# OSO-SWAT-A1-00.net
KiCad netlist of a schematic drawn in EAGLE
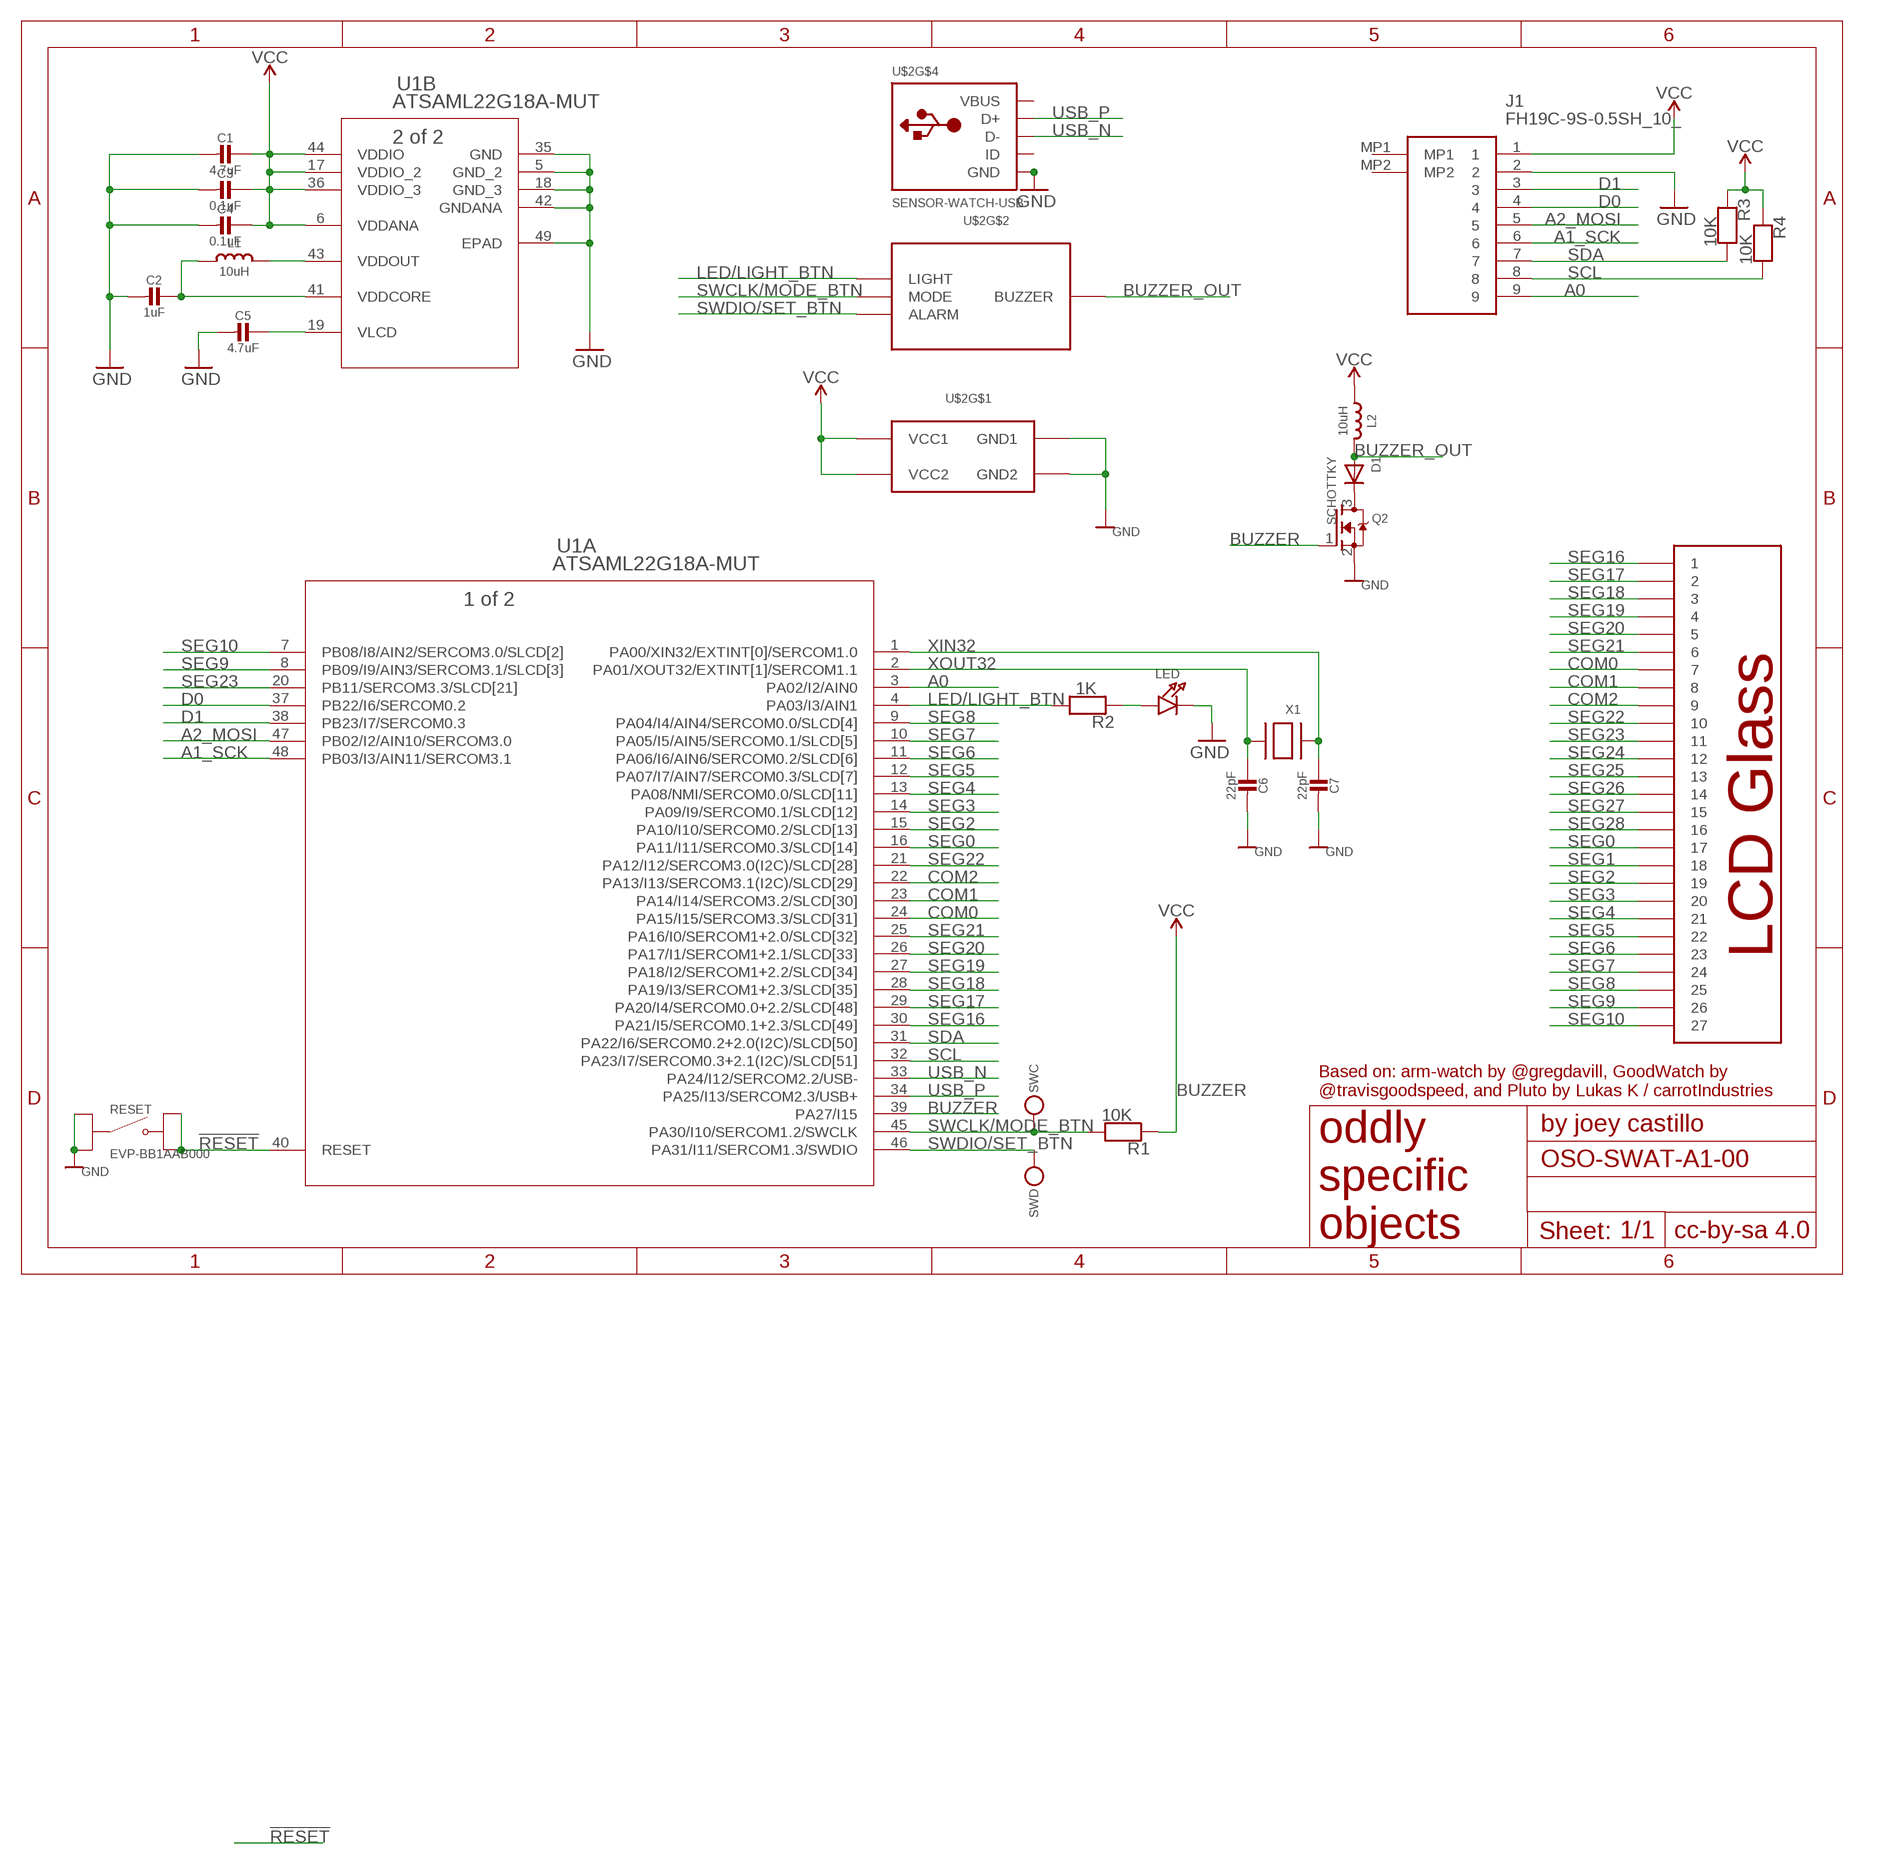
[diagram p0: schematic, sheet 1]

(export (version "E")
  (design (tool "Eeschema 10.0.6"))
  (components
    (comp (ref "C1")
      (value "4.7uF")
      (footprint "eagle-import:_0603MP")
      (libsource (lib "eagle-import") (part "CAP_CERAMIC_0603MP"))
    )
    (comp (ref "C2")
      (value "1uF")
      (footprint "eagle-import:_0603MP")
      (libsource (lib "eagle-import") (part "CAP_CERAMIC_0603MP"))
    )
    (comp (ref "C3")
      (value "0.1uF")
      (footprint "eagle-import:_0603MP")
      (libsource (lib "eagle-import") (part "CAP_CERAMIC_0603MP"))
    )
    (comp (ref "C4")
      (value "0.1uF")
      (footprint "eagle-import:_0603MP")
      (libsource (lib "eagle-import") (part "CAP_CERAMIC_0603MP"))
    )
    (comp (ref "C5")
      (value "4.7uF")
      (footprint "eagle-import:_0603MP")
      (libsource (lib "eagle-import") (part "CAP_CERAMIC_0603MP"))
    )
    (comp (ref "C6")
      (value "22pF")
      (footprint "eagle-import:_0603MP")
      (libsource (lib "eagle-import") (part "CAP_CERAMIC_0603MP"))
    )
    (comp (ref "C7")
      (value "22pF")
      (footprint "eagle-import:_0603MP")
      (libsource (lib "eagle-import") (part "CAP_CERAMIC_0603MP"))
    )
    (comp (ref "D1")
      (value "SCHOTTKY")
      (footprint "eagle-import:SOD-323F")
      (libsource (lib "eagle-import") (part "DIODESOD-323F"))
    )
    (comp (ref "J1")
      (value "FH19C-9S-0.5SH_10_")
      (footprint "eagle-import:FH19C9S05SH10")
      (fields
        (field (name "MANUFACTURER_PART_NUMBER") "FH19C-9S-0.5SH(10)")
        (field (name "MOUSER_PART_NUMBER") "798-FH19C9S05SH10")
      )
      (libsource (lib "eagle-import") (part "FH19C-9S-0.5SH_10_"))
    )
    (comp (ref "L1")
      (value "10uH")
      (footprint "eagle-import:MICROBUILDER__0805MP")
      (libsource (lib "eagle-import") (part "MICROBUILDER_INDUCTOR_0805MP"))
    )
    (comp (ref "L2")
      (value "10uH")
      (footprint "eagle-import:MICROBUILDER__0805MP")
      (libsource (lib "eagle-import") (part "MICROBUILDER_INDUCTOR_0805MP"))
    )
    (comp (ref "LED")
      (value "LED0805_NOOUTLINE")
      (footprint "eagle-import:CHIPLED_0805_NOOUTLINE")
      (libsource (lib "eagle-import") (part "LED0805_NOOUTLINE"))
    )
    (comp (ref "Q2")
      (value "MOSFET-NREFLOW")
      (footprint "eagle-import:SOT23-R")
      (libsource (lib "eagle-import") (part "MOSFET-NREFLOW"))
    )
    (comp (ref "R1")
      (value "10K")
      (footprint "eagle-import:_0603MP")
      (libsource (lib "eagle-import") (part "RESISTOR_0603MP"))
    )
    (comp (ref "R2")
      (value "1K")
      (footprint "eagle-import:_0603MP")
      (libsource (lib "eagle-import") (part "RESISTOR_0603MP"))
    )
    (comp (ref "R3")
      (value "10K")
      (footprint "eagle-import:_0603MP")
      (libsource (lib "eagle-import") (part "RESISTOR_0603MP"))
    )
    (comp (ref "R4")
      (value "10K")
      (footprint "eagle-import:_0603MP")
      (libsource (lib "eagle-import") (part "RESISTOR_0603MP"))
    )
    (comp (ref "RESET")
      (value "EVP-BB1AAB000")
      (footprint "eagle-import:SW_EVP-BB1AAB000")
      (fields
        (field (name "DIGI-KEY_PART_NUMBER") "P124390CT-ND")
        (field (name "MF") "Panasonic Electronic Components")
      )
      (libsource (lib "eagle-import") (part "EVP-BB1AAB000"))
    )
    (comp (ref "SWC")
      (value "MICROBUILDER_TESTPOINTPAD1MM")
      (footprint "eagle-import:MICROBUILDER_TESTPOINT_PAD_1MM")
      (libsource (lib "eagle-import") (part "MICROBUILDER_TESTPOINTPAD1MM"))
    )
    (comp (ref "SWD")
      (value "MICROBUILDER_TESTPOINTPAD1MM")
      (footprint "eagle-import:MICROBUILDER_TESTPOINT_PAD_1MM")
      (libsource (lib "eagle-import") (part "MICROBUILDER_TESTPOINTPAD1MM"))
    )
    (comp (ref "U$2")
      (value "SENSOR-WATCH-USB")
      (footprint "eagle-import:CASIO-F91W-OUTLINE-USB")
      (libsource (lib "eagle-import") (part "SENSOR-WATCH-USB"))
    )
    (comp (ref "U1")
      (value "ATSAML22G18A-MUT")
      (footprint "eagle-import:QFN48_7X7MC_MCH")
      (fields (field (name "COPYRIGHT") "Copyright (C) 2018 Accelerated Designs. All rights reserved"))
      (libsource (lib "eagle-import") (part "ATSAML22G18A-MUT"))
    )
    (comp (ref "X1")
      (value "XTAL-3.2X1.5")
      (footprint "eagle-import:XTAL3215")
      (libsource (lib "eagle-import") (part "XTAL-3.2X1.5"))
    )
  )
  (nets
    (net (code "1") (name "/A0") (class "Default")
      (node (ref "J1") (pin "9") (pinfunction "9_9") (pintype "bidirectional"))
      (node (ref "U1") (pin "3") (pinfunction "PA02/I2/AIN0_3") (pintype "bidirectional"))
    )
    (net (code "2") (name "/A1_SCK") (class "Default")
      (node (ref "J1") (pin "6") (pinfunction "6_6") (pintype "bidirectional"))
      (node (ref "U1") (pin "48") (pinfunction "PB03/I3/AIN11/SERCOM3.1_48") (pintype "bidirectional"))
    )
    (net (code "3") (name "/A2_MOSI") (class "Default")
      (node (ref "J1") (pin "5") (pinfunction "5_5") (pintype "bidirectional"))
      (node (ref "U1") (pin "47") (pinfunction "PB02/I2/AIN10/SERCOM3.0_47") (pintype "bidirectional"))
    )
    (net (code "4") (name "/BUZZER") (class "Default")
      (node (ref "Q2") (pin "1") (pinfunction "G_1") (pintype "bidirectional"))
      (node (ref "U1") (pin "39") (pinfunction "PA27/I15_39") (pintype "bidirectional"))
    )
    (net (code "5") (name "/BUZZER_OUT") (class "Default")
      (node (ref "D1") (pin "A") (pinfunction "A_A") (pintype "passive"))
      (node (ref "L2") (pin "2") (pinfunction "2_2") (pintype "passive"))
      (node (ref "U$2") (pin "BUZZER") (pinfunction "BUZZER_BUZZER") (pintype "bidirectional"))
    )
    (net (code "6") (name "/COM0") (class "Default")
      (node (ref "U$2") (pin "7") (pinfunction "7_7") (pintype "input"))
      (node (ref "U1") (pin "24") (pinfunction "PA15/I15/SERCOM3.3/SLCD[31]_24") (pintype "bidirectional"))
    )
    (net (code "7") (name "/COM1") (class "Default")
      (node (ref "U$2") (pin "8") (pinfunction "8_8") (pintype "input"))
      (node (ref "U1") (pin "23") (pinfunction "PA14/I14/SERCOM3.2/SLCD[30]_23") (pintype "bidirectional"))
    )
    (net (code "8") (name "/COM2") (class "Default")
      (node (ref "U$2") (pin "9") (pinfunction "9_9") (pintype "input"))
      (node (ref "U1") (pin "22") (pinfunction "PA13/I13/SERCOM3.1(I2C)/SLCD[29]_22") (pintype "bidirectional"))
    )
    (net (code "9") (name "/D0") (class "Default")
      (node (ref "J1") (pin "4") (pinfunction "4_4") (pintype "bidirectional"))
      (node (ref "U1") (pin "37") (pinfunction "PB22/I6/SERCOM0.2_37") (pintype "bidirectional"))
    )
    (net (code "10") (name "/D1") (class "Default")
      (node (ref "J1") (pin "3") (pinfunction "3_3") (pintype "bidirectional"))
      (node (ref "U1") (pin "38") (pinfunction "PB23/I7/SERCOM0.3_38") (pintype "bidirectional"))
    )
    (net (code "11") (name "/LED{slash}LIGHT_BTN") (class "Default")
      (node (ref "R2") (pin "2") (pinfunction "2_2") (pintype "passive"))
      (node (ref "U$2") (pin "LIGHT") (pinfunction "LIGHT_LIGHT") (pintype "bidirectional"))
      (node (ref "U1") (pin "4") (pinfunction "PA03/I3/AIN1_4") (pintype "bidirectional"))
    )
    (net (code "12") (name "/SCL") (class "Default")
      (node (ref "J1") (pin "8") (pinfunction "8_8") (pintype "bidirectional"))
      (node (ref "R4") (pin "2") (pinfunction "2_2") (pintype "passive"))
      (node (ref "U1") (pin "32") (pinfunction "PA23/I7/SERCOM0.3+2.1(I2C)/SLCD[51]_32") (pintype "bidirectional"))
    )
    (net (code "13") (name "/SDA") (class "Default")
      (node (ref "J1") (pin "7") (pinfunction "7_7") (pintype "bidirectional"))
      (node (ref "R3") (pin "2") (pinfunction "2_2") (pintype "passive"))
      (node (ref "U1") (pin "31") (pinfunction "PA22/I6/SERCOM0.2+2.0(I2C)/SLCD[50]_31") (pintype "bidirectional"))
    )
    (net (code "14") (name "/SEG0") (class "Default")
      (node (ref "U$2") (pin "17") (pinfunction "17_17") (pintype "input"))
      (node (ref "U1") (pin "16") (pinfunction "PA11/I11/SERCOM0.3/SLCD[14]_16") (pintype "bidirectional"))
    )
    (net (code "15") (name "/SEG1") (class "Default")
      (node (ref "U$2") (pin "18") (pinfunction "18_18") (pintype "input"))
    )
    (net (code "16") (name "/SEG2") (class "Default")
      (node (ref "U$2") (pin "19") (pinfunction "19_19") (pintype "input"))
      (node (ref "U1") (pin "15") (pinfunction "PA10/I10/SERCOM0.2/SLCD[13]_15") (pintype "bidirectional"))
    )
    (net (code "17") (name "/SEG3") (class "Default")
      (node (ref "U$2") (pin "20") (pinfunction "20_20") (pintype "input"))
      (node (ref "U1") (pin "14") (pinfunction "PA09/I9/SERCOM0.1/SLCD[12]_14") (pintype "bidirectional"))
    )
    (net (code "18") (name "/SEG4") (class "Default")
      (node (ref "U$2") (pin "21") (pinfunction "21_21") (pintype "input"))
      (node (ref "U1") (pin "13") (pinfunction "PA08/NMI/SERCOM0.0/SLCD[11]_13") (pintype "bidirectional"))
    )
    (net (code "19") (name "/SEG5") (class "Default")
      (node (ref "U$2") (pin "22") (pinfunction "22_22") (pintype "input"))
      (node (ref "U1") (pin "12") (pinfunction "PA07/I7/AIN7/SERCOM0.3/SLCD[7]_12") (pintype "bidirectional"))
    )
    (net (code "20") (name "/SEG6") (class "Default")
      (node (ref "U$2") (pin "23") (pinfunction "23_23") (pintype "input"))
      (node (ref "U1") (pin "11") (pinfunction "PA06/I6/AIN6/SERCOM0.2/SLCD[6]_11") (pintype "bidirectional"))
    )
    (net (code "21") (name "/SEG7") (class "Default")
      (node (ref "U$2") (pin "24") (pinfunction "24_24") (pintype "input"))
      (node (ref "U1") (pin "10") (pinfunction "PA05/I5/AIN5/SERCOM0.1/SLCD[5]_10") (pintype "bidirectional"))
    )
    (net (code "22") (name "/SEG8") (class "Default")
      (node (ref "U$2") (pin "25") (pinfunction "25_25") (pintype "input"))
      (node (ref "U1") (pin "9") (pinfunction "PA04/I4/AIN4/SERCOM0.0/SLCD[4]_9") (pintype "bidirectional"))
    )
    (net (code "23") (name "/SEG9") (class "Default")
      (node (ref "U$2") (pin "26") (pinfunction "26_26") (pintype "input"))
      (node (ref "U1") (pin "8") (pinfunction "PB09/I9/AIN3/SERCOM3.1/SLCD[3]_8") (pintype "bidirectional"))
    )
    (net (code "24") (name "/SEG10") (class "Default")
      (node (ref "U$2") (pin "27") (pinfunction "27_27") (pintype "input"))
      (node (ref "U1") (pin "7") (pinfunction "PB08/I8/AIN2/SERCOM3.0/SLCD[2]_7") (pintype "bidirectional"))
    )
    (net (code "25") (name "/SEG16") (class "Default")
      (node (ref "U$2") (pin "1") (pinfunction "1_1") (pintype "input"))
      (node (ref "U1") (pin "30") (pinfunction "PA21/I5/SERCOM0.1+2.3/SLCD[49]_30") (pintype "bidirectional"))
    )
    (net (code "26") (name "/SEG17") (class "Default")
      (node (ref "U$2") (pin "2") (pinfunction "2_2") (pintype "input"))
      (node (ref "U1") (pin "29") (pinfunction "PA20/I4/SERCOM0.0+2.2/SLCD[48]_29") (pintype "bidirectional"))
    )
    (net (code "27") (name "/SEG18") (class "Default")
      (node (ref "U$2") (pin "3") (pinfunction "3_3") (pintype "input"))
      (node (ref "U1") (pin "28") (pinfunction "PA19/I3/SERCOM1+2.3/SLCD[35]_28") (pintype "bidirectional"))
    )
    (net (code "28") (name "/SEG19") (class "Default")
      (node (ref "U$2") (pin "4") (pinfunction "4_4") (pintype "input"))
      (node (ref "U1") (pin "27") (pinfunction "PA18/I2/SERCOM1+2.2/SLCD[34]_27") (pintype "bidirectional"))
    )
    (net (code "29") (name "/SEG20") (class "Default")
      (node (ref "U$2") (pin "5") (pinfunction "5_5") (pintype "input"))
      (node (ref "U1") (pin "26") (pinfunction "PA17/I1/SERCOM1+2.1/SLCD[33]_26") (pintype "bidirectional"))
    )
    (net (code "30") (name "/SEG21") (class "Default")
      (node (ref "U$2") (pin "6") (pinfunction "6_6") (pintype "input"))
      (node (ref "U1") (pin "25") (pinfunction "PA16/I0/SERCOM1+2.0/SLCD[32]_25") (pintype "bidirectional"))
    )
    (net (code "31") (name "/SEG22") (class "Default")
      (node (ref "U$2") (pin "10") (pinfunction "10_10") (pintype "input"))
      (node (ref "U1") (pin "21") (pinfunction "PA12/I12/SERCOM3.0(I2C)/SLCD[28]_21") (pintype "bidirectional"))
    )
    (net (code "32") (name "/SEG23") (class "Default")
      (node (ref "U$2") (pin "11") (pinfunction "11_11") (pintype "input"))
      (node (ref "U1") (pin "20") (pinfunction "PB11/SERCOM3.3/SLCD[21]_20") (pintype "bidirectional"))
    )
    (net (code "33") (name "/SEG24") (class "Default")
      (node (ref "U$2") (pin "12") (pinfunction "12_12") (pintype "input"))
    )
    (net (code "34") (name "/SEG25") (class "Default")
      (node (ref "U$2") (pin "13") (pinfunction "13_13") (pintype "input"))
    )
    (net (code "35") (name "/SEG26") (class "Default")
      (node (ref "U$2") (pin "14") (pinfunction "14_14") (pintype "input"))
    )
    (net (code "36") (name "/SEG27") (class "Default")
      (node (ref "U$2") (pin "15") (pinfunction "15_15") (pintype "input"))
    )
    (net (code "37") (name "/SEG28") (class "Default")
      (node (ref "U$2") (pin "16") (pinfunction "16_16") (pintype "input"))
    )
    (net (code "38") (name "/SWCLK{slash}MODE_BTN") (class "Default")
      (node (ref "R1") (pin "2") (pinfunction "2_2") (pintype "passive"))
      (node (ref "SWC") (pin "P$1") (pinfunction "P$1_P$1") (pintype "bidirectional"))
      (node (ref "U$2") (pin "MODE") (pinfunction "MODE_MODE") (pintype "bidirectional"))
      (node (ref "U1") (pin "45") (pinfunction "PA30/I10/SERCOM1.2/SWCLK_45") (pintype "bidirectional"))
    )
    (net (code "39") (name "/SWDIO{slash}SET_BTN") (class "Default")
      (node (ref "SWD") (pin "P$1") (pinfunction "P$1_P$1") (pintype "bidirectional"))
      (node (ref "U$2") (pin "ALARM") (pinfunction "ALARM_ALARM") (pintype "bidirectional"))
      (node (ref "U1") (pin "46") (pinfunction "PA31/I11/SERCOM1.3/SWDIO_46") (pintype "bidirectional"))
    )
    (net (code "40") (name "/USB_N") (class "Default")
      (node (ref "U$2") (pin "USB_N") (pinfunction "D-_USB_N") (pintype "bidirectional"))
      (node (ref "U1") (pin "33") (pinfunction "PA24/I12/SERCOM2.2/USB-_33") (pintype "bidirectional"))
    )
    (net (code "41") (name "/USB_P") (class "Default")
      (node (ref "U$2") (pin "USB_P") (pinfunction "D+_USB_P") (pintype "bidirectional"))
      (node (ref "U1") (pin "34") (pinfunction "PA25/I13/SERCOM2.3/USB+_34") (pintype "bidirectional"))
    )
    (net (code "42") (name "/VBUS") (class "Default")
      (node (ref "U$2") (pin "VBUS") (pinfunction "VBUS_VBUS") (pintype "power_in"))
    )
    (net (code "43") (name "/XIN32") (class "Default")
      (node (ref "C7") (pin "1") (pinfunction "1_1") (pintype "passive"))
      (node (ref "U1") (pin "1") (pinfunction "PA00/XIN32/EXTINT[0]/SERCOM1.0_1") (pintype "bidirectional"))
      (node (ref "X1") (pin "P$1") (pinfunction "P$1_P$1") (pintype "bidirectional"))
    )
    (net (code "44") (name "/XOUT32") (class "Default")
      (node (ref "C6") (pin "1") (pinfunction "1_1") (pintype "passive"))
      (node (ref "U1") (pin "2") (pinfunction "PA01/XOUT32/EXTINT[1]/SERCOM1.1_2") (pintype "bidirectional"))
      (node (ref "X1") (pin "P$2") (pinfunction "P$2_P$2") (pintype "bidirectional"))
    )
    (net (code "45") (name "/~{RESET}") (class "Default")
      (node (ref "RESET") (pin "B1") (pinfunction "B1_B1") (pintype "passive"))
      (node (ref "RESET") (pin "B2") (pinfunction "B2_B2") (pintype "passive"))
      (node (ref "U1") (pin "40") (pinfunction "RESET_40") (pintype "passive"))
    )
    (net (code "46") (name "GND") (class "Default")
      (node (ref "C1") (pin "2") (pinfunction "2_2") (pintype "passive"))
      (node (ref "C2") (pin "2") (pinfunction "2_2") (pintype "passive"))
      (node (ref "C3") (pin "2") (pinfunction "2_2") (pintype "passive"))
      (node (ref "C4") (pin "2") (pinfunction "2_2") (pintype "passive"))
      (node (ref "C5") (pin "2") (pinfunction "2_2") (pintype "passive"))
      (node (ref "C6") (pin "2") (pinfunction "2_2") (pintype "passive"))
      (node (ref "C7") (pin "2") (pinfunction "2_2") (pintype "passive"))
      (node (ref "J1") (pin "2") (pinfunction "2_2") (pintype "bidirectional"))
      (node (ref "LED") (pin "C") (pinfunction "C_C") (pintype "passive"))
      (node (ref "Q2") (pin "2") (pinfunction "S_2") (pintype "bidirectional"))
      (node (ref "RESET") (pin "A1") (pinfunction "A1_A1") (pintype "passive"))
      (node (ref "RESET") (pin "A2") (pinfunction "A2_A2") (pintype "passive"))
      (node (ref "U$2") (pin "GND") (pinfunction "GND_GND") (pintype "power_in"))
      (node (ref "U$2") (pin "GND1") (pinfunction "GND1_GND1") (pintype "bidirectional"))
      (node (ref "U$2") (pin "GND2") (pinfunction "GND2_GND2") (pintype "bidirectional"))
      (node (ref "U1") (pin "18") (pinfunction "GND_3_18") (pintype "passive"))
      (node (ref "U1") (pin "35") (pinfunction "GND_35") (pintype "passive"))
      (node (ref "U1") (pin "42") (pinfunction "GNDANA_42") (pintype "passive"))
      (node (ref "U1") (pin "49") (pinfunction "EPAD_49") (pintype "passive"))
      (node (ref "U1") (pin "5") (pinfunction "GND_2_5") (pintype "passive"))
    )
    (net (code "47") (name "Net-(LED-PadA)") (class "Default")
      (node (ref "LED") (pin "A") (pinfunction "A_A") (pintype "passive"))
      (node (ref "R2") (pin "1") (pinfunction "1_1") (pintype "passive"))
    )
    (net (code "48") (name "Net-(Q2-D)") (class "Default")
      (node (ref "D1") (pin "C") (pinfunction "C_C") (pintype "passive"))
      (node (ref "Q2") (pin "3") (pinfunction "D_3") (pintype "bidirectional"))
    )
    (net (code "49") (name "Net-(U1B-VDDCORE)") (class "Default")
      (node (ref "C2") (pin "1") (pinfunction "1_1") (pintype "passive"))
      (node (ref "L1") (pin "1") (pinfunction "1_1") (pintype "passive"))
      (node (ref "U1") (pin "41") (pinfunction "VDDCORE_41") (pintype "power_in"))
    )
    (net (code "50") (name "Net-(U1B-VDDOUT)") (class "Default")
      (node (ref "L1") (pin "2") (pinfunction "2_2") (pintype "passive"))
      (node (ref "U1") (pin "43") (pinfunction "VDDOUT_43") (pintype "output"))
    )
    (net (code "51") (name "Net-(U1B-VLCD)") (class "Default")
      (node (ref "C5") (pin "1") (pinfunction "1_1") (pintype "passive"))
      (node (ref "U1") (pin "19") (pinfunction "VLCD_19") (pintype "passive"))
    )
    (net (code "52") (name "VCC") (class "Default")
      (node (ref "C1") (pin "1") (pinfunction "1_1") (pintype "passive"))
      (node (ref "C3") (pin "1") (pinfunction "1_1") (pintype "passive"))
      (node (ref "C4") (pin "1") (pinfunction "1_1") (pintype "passive"))
      (node (ref "J1") (pin "1") (pinfunction "1_1") (pintype "bidirectional"))
      (node (ref "L2") (pin "1") (pinfunction "1_1") (pintype "passive"))
      (node (ref "R1") (pin "1") (pinfunction "1_1") (pintype "passive"))
      (node (ref "R3") (pin "1") (pinfunction "1_1") (pintype "passive"))
      (node (ref "R4") (pin "1") (pinfunction "1_1") (pintype "passive"))
      (node (ref "U$2") (pin "VCC1") (pinfunction "VCC1_VCC1") (pintype "bidirectional"))
      (node (ref "U$2") (pin "VCC2") (pinfunction "VCC2_VCC2") (pintype "bidirectional"))
      (node (ref "U1") (pin "17") (pinfunction "VDDIO_2_17") (pintype "power_in"))
      (node (ref "U1") (pin "36") (pinfunction "VDDIO_3_36") (pintype "power_in"))
      (node (ref "U1") (pin "44") (pinfunction "VDDIO_44") (pintype "power_in"))
      (node (ref "U1") (pin "6") (pinfunction "VDDANA_6") (pintype "power_in"))
    )
    (net (code "53") (name "unconnected-(J1-PadMP1)") (class "Default")
      (node (ref "J1") (pin "MP1") (pinfunction "MP1_MP1") (pintype "bidirectional"))
    )
    (net (code "54") (name "unconnected-(J1-PadMP2)") (class "Default")
      (node (ref "J1") (pin "MP2") (pinfunction "MP2_MP2") (pintype "bidirectional"))
    )
    (net (code "55") (name "unconnected-(U$2D-ID-PadUSB_ID)") (class "Default")
      (node (ref "U$2") (pin "USB_ID") (pinfunction "ID_USB_ID") (pintype "bidirectional"))
    )
  )
)
